# STM32_Peripherals.net
KiCad netlist of a schematic drawn in Altium Designer
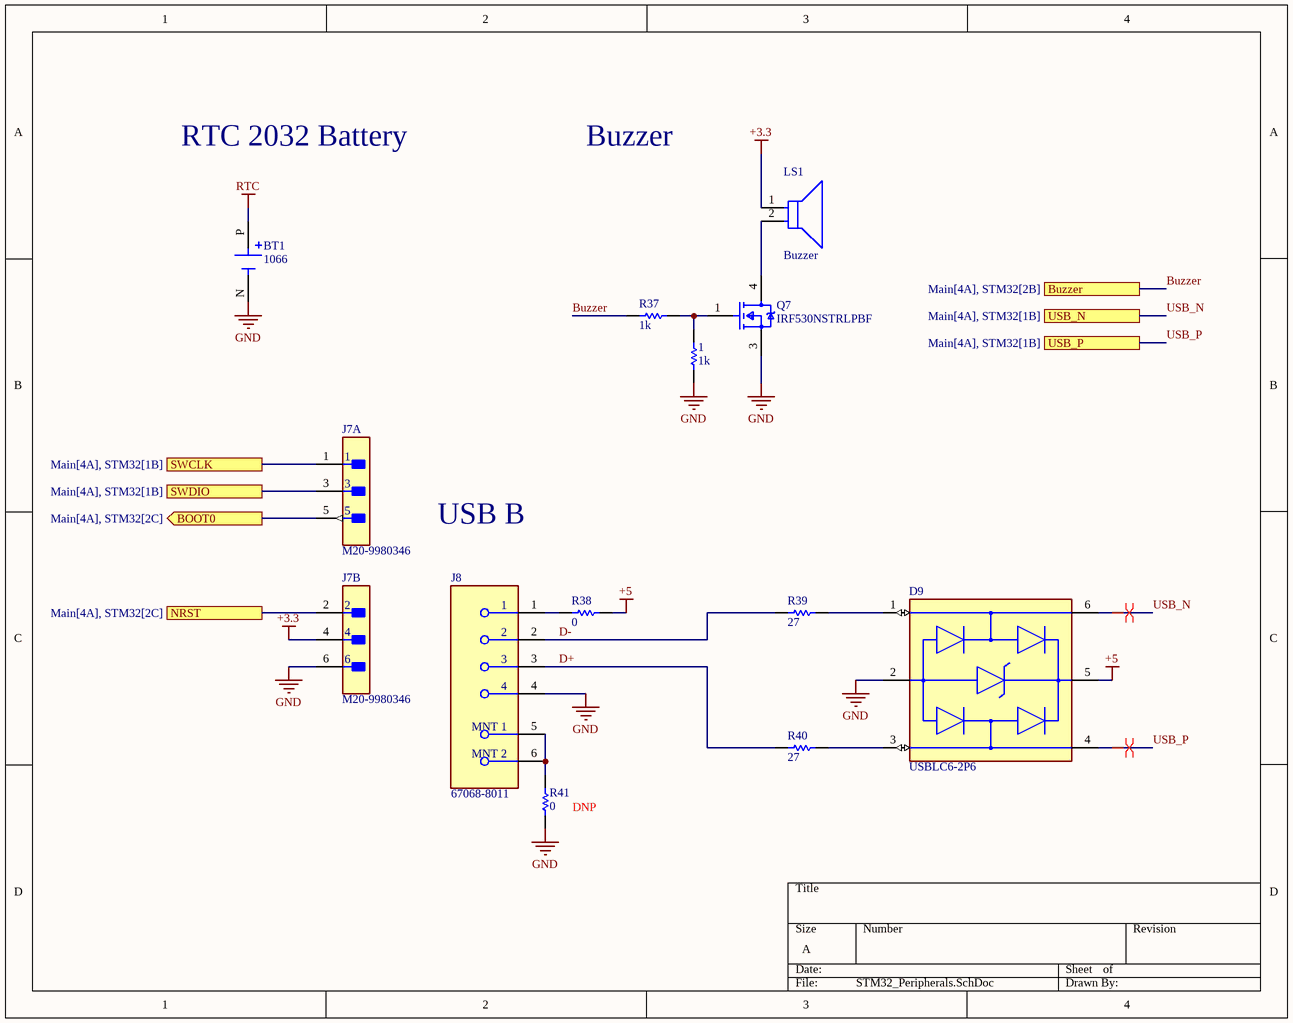
[diagram p0: STM32_Peripherals.SchDoc]

(export (version "E")
  (design (tool "Eeschema 10.0.6"))
  (components
    (comp (ref "1")
      (value "1k")
      (footprint "RESC2013X50X30LL20T20")
      (fields (field (name "MANUFACTURER") "Vishay Dale") (field (name "PART NUMBER") "CRCW08050000Z0EA"))
      (libsource (lib "Altium Content Vault") (part "RES"))
    )
    (comp (ref "BT1") (value "1066") (footprint "BAT_1066") (libsource (lib "1066") (part "1066")))
    (comp (ref "D9")
      (value "USBLC6-2P6")
      (footprint "FP-SOT-666-MFG")
      (description "TVS DIODE 5.25V 17V SOT666")
      (libsource (lib "Altium Content Vault") (part "c871e55f7e3243d341edbd671b98d92"))
    )
    (comp (ref "J7")
      (value "M20-9980346")
      (footprint "FP-M20-9980346-MFG")
      (description "CONN HEADER VERT 6POS 2.54MM")
      (fields
        (field (name "MANUFACTURER") "Harwin")
        (field (name "OCTOPART") "https://octopart.com/m20-9980346-harwin-5436545")
      )
      (libsource (lib "Altium Content Vault") (part "2654a11fb13586ecb194516b1c997bc"))
    )
    (comp (ref "J8")
      (value "67068-8011")
      (footprint "FP-67068-8011-MFG")
      (description "67068-8011 Conn USB 2.0 Type B RCP 4 POS 2.5mm Solder RA Thru-Hole 4 Terminal 1 Port USB 2.0 Tray")
      (libsource (lib "Altium Content Vault") (part "79e6714efa0bb2f851c24b2688127c9"))
    )
    (comp (ref "LS1")
      (value "Buzzer")
      (footprint "FP-PKB24SPCH3601-B0-MFG")
      (description "AUDIO PIEZO TRANSDUCER 3-15V TH")
      (libsource (lib "Altium Content Vault") (part "1973c4b650225fd2ddacaff6b763965"))
    )
    (comp (ref "Q7")
      (value "IRF530NSTRLPBF")
      (footprint "FP-PG-TO263-3-MFG")
      (description "MOSFET N-CH 100V 17A D2PAK")
      (fields
        (field (name "OCTOPART") "https://octopart.com/irf530nstrlpbf-infineon-65873402")
        (field (name "MANUFACTURER") "Infineon")
      )
      (libsource (lib "Altium Content Vault") (part "cdf1c68f84cb049e5ebc85739c3fcf6"))
    )
    (comp (ref "R37")
      (value "1k")
      (footprint "RESC2013X50X30LL20T20")
      (fields (field (name "MANUFACTURER") "Vishay Dale") (field (name "PART NUMBER") "CRCW08050000Z0EA"))
      (libsource (lib "Altium Content Vault") (part "RES"))
    )
    (comp (ref "R38")
      (value "0")
      (footprint "RESC2013X50X30LL20T20")
      (fields (field (name "MANUFACTURER") "Vishay Dale") (field (name "PART NUMBER") "CRCW08050000Z0EA"))
      (libsource (lib "Altium Content Vault") (part "RES"))
    )
    (comp (ref "R39")
      (value "27")
      (footprint "RESC2013X50X30LL20T20")
      (fields (field (name "MANUFACTURER") "Vishay Dale") (field (name "PART NUMBER") "CRCW08050000Z0EA"))
      (libsource (lib "Altium Content Vault") (part "RES"))
    )
    (comp (ref "R40")
      (value "27")
      (footprint "RESC2013X50X30LL20T20")
      (fields (field (name "MANUFACTURER") "Vishay Dale") (field (name "PART NUMBER") "CRCW08050000Z0EA"))
      (libsource (lib "Altium Content Vault") (part "RES"))
    )
    (comp (ref "R41")
      (value "0")
      (footprint "RESC2013X50X30LL20T20")
      (fields (field (name "MANUFACTURER") "Vishay Dale") (field (name "PART NUMBER") "CRCW08050000Z0EA"))
      (libsource (lib "Altium Content Vault") (part "RES"))
    )
  )
  (nets
    (net (code "1") (name "+3.3") (class "Default")
      (node (ref "J7") (pin "4") (pinfunction "4_4") (pintype "passive"))
      (node (ref "LS1") (pin "1") (pinfunction "C_1") (pintype "passive"))
    )
    (net (code "2") (name "+5") (class "Default")
      (node (ref "D9") (pin "5") (pinfunction "VBUS_5") (pintype "power_in"))
      (node (ref "R38") (pin "2") (pinfunction "2_2") (pintype "passive"))
    )
    (net (code "4") (name "/BOOT0") (class "Default")
      (node (ref "J7") (pin "5") (pinfunction "5_5") (pintype "output"))
    )
    (net (code "5") (name "/Buzzer") (class "Default")
      (node (ref "R37") (pin "1") (pinfunction "1_1") (pintype "passive"))
    )
    (net (code "6") (name "/D+") (class "Default")
      (node (ref "J8") (pin "3") (pinfunction "3_3") (pintype "passive"))
      (node (ref "R40") (pin "1") (pinfunction "1_1") (pintype "passive"))
    )
    (net (code "7") (name "/D-") (class "Default")
      (node (ref "J8") (pin "2") (pinfunction "2_2") (pintype "passive"))
      (node (ref "R39") (pin "1") (pinfunction "1_1") (pintype "passive"))
    )
    (net (code "8") (name "/NRST") (class "Default")
      (node (ref "J7") (pin "2") (pinfunction "2_2") (pintype "passive"))
    )
    (net (code "9") (name "/SWCLK") (class "Default")
      (node (ref "J7") (pin "1") (pinfunction "1_1") (pintype "passive"))
    )
    (net (code "10") (name "/SWDIO") (class "Default")
      (node (ref "J7") (pin "3") (pinfunction "3_3") (pintype "passive"))
    )
    (net (code "11") (name "/USB_N") (class "Default")
      (node (ref "D9") (pin "6") (pinfunction "I/O1_6") (pintype "passive"))
    )
    (net (code "12") (name "/USB_P") (class "Default")
      (node (ref "D9") (pin "4") (pinfunction "I/O2_4") (pintype "passive"))
    )
    (net (code "13") (name "GND") (class "Default")
      (node (ref "1") (pin "1") (pinfunction "1_1") (pintype "passive"))
      (node (ref "BT1") (pin "N") (pinfunction "NEG_N") (pintype "passive"))
      (node (ref "D9") (pin "2") (pinfunction "GND_2") (pintype "power_in"))
      (node (ref "J7") (pin "6") (pinfunction "6_6") (pintype "passive"))
      (node (ref "J8") (pin "4") (pinfunction "4_4") (pintype "passive"))
      (node (ref "Q7") (pin "3") (pinfunction "S_3") (pintype "passive"))
      (node (ref "R41") (pin "1") (pinfunction "1_1") (pintype "passive"))
    )
    (net (code "14") (name "Net-(D9-I{slash}O1-Pad1)") (class "Default")
      (node (ref "D9") (pin "1") (pinfunction "I/O1_1") (pintype "bidirectional"))
      (node (ref "R39") (pin "2") (pinfunction "2_2") (pintype "passive"))
    )
    (net (code "15") (name "Net-(D9-I{slash}O2-Pad3)") (class "Default")
      (node (ref "D9") (pin "3") (pinfunction "I/O2_3") (pintype "bidirectional"))
      (node (ref "R40") (pin "2") (pinfunction "2_2") (pintype "passive"))
    )
    (net (code "16") (name "Net-(J8-MNT_1)") (class "Default")
      (node (ref "J8") (pin "5") (pinfunction "MNT_1_5") (pintype "passive"))
      (node (ref "J8") (pin "6") (pinfunction "MNT_2_6") (pintype "passive"))
      (node (ref "R41") (pin "2") (pinfunction "2_2") (pintype "passive"))
    )
    (net (code "17") (name "Net-(J8-Pad1)") (class "Default")
      (node (ref "J8") (pin "1") (pinfunction "1_1") (pintype "passive"))
      (node (ref "R38") (pin "1") (pinfunction "1_1") (pintype "passive"))
    )
    (net (code "18") (name "Net-(LS1-A)") (class "Default")
      (node (ref "LS1") (pin "2") (pinfunction "A_2") (pintype "passive"))
      (node (ref "Q7") (pin "4") (pinfunction "D_4") (pintype "passive"))
    )
    (net (code "19") (name "Net-(Q7-G)") (class "Default")
      (node (ref "1") (pin "2") (pinfunction "2_2") (pintype "passive"))
      (node (ref "Q7") (pin "1") (pinfunction "G_1") (pintype "passive"))
      (node (ref "R37") (pin "2") (pinfunction "2_2") (pintype "passive"))
    )
    (net (code "20") (name "RTC") (class "Default")
      (node (ref "BT1") (pin "P") (pinfunction "POS_P") (pintype "passive"))
    )
  )
)
